# FPGA_IO.net
KiCad netlist of a schematic drawn in Altium Designer
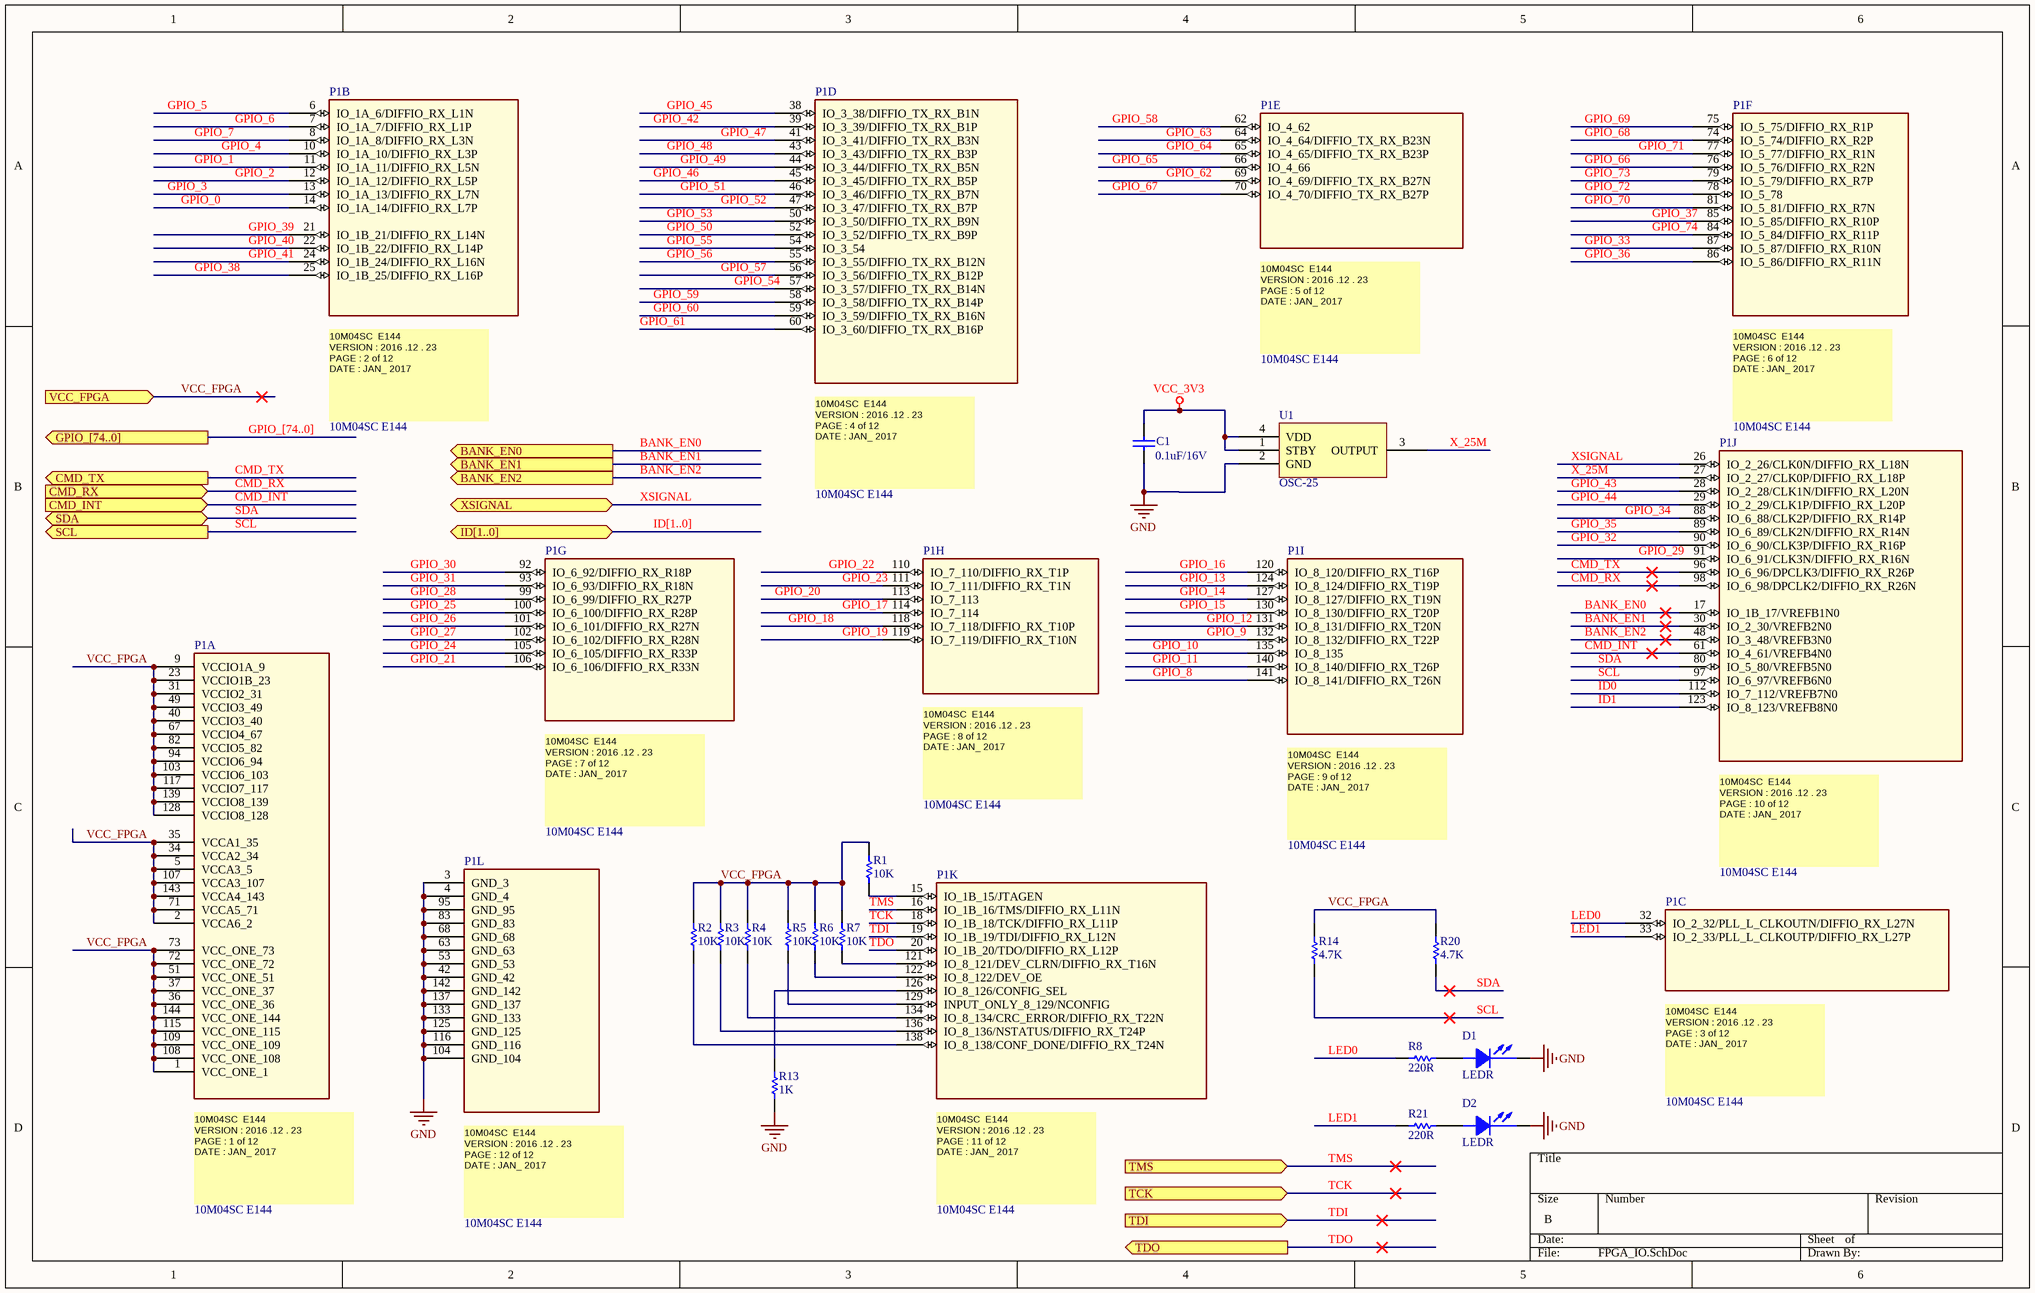
[diagram p0: FPGA_IO.SchDoc]

(export (version "E")
  (design (tool "Eeschema 10.0.6"))
  (components
    (comp (ref "C1")
      (value "0.1uF/16V")
      (footprint "0603C")
      (description "Multilayer Ceramic Capacitors MLCC - SMD/SMT 0603 16VDC 0.1uF 10% X7R AEC-Q200")
      (fields (field (name "MFR") "Taiyo Yuden") (field (name "MFR PART NO") "EMK107B7104KAHT"))
      (libsource (lib "Miscellaneous Devices") (part "Cap"))
    )
    (comp (ref "D1")
      (value "LEDR")
      (footprint "LED_0603")
      (description "Standard LEDs - SMD Red 631nm 14mcd 5mA")
      (fields (field (name "MFR") "Lite-On") (field (name "MFR PART NO") "LTST-C193KRKT-5A"))
      (libsource (lib "de20") (part "LED"))
    )
    (comp (ref "D2")
      (value "LEDR")
      (footprint "LED_0603")
      (description "Standard LEDs - SMD Red 631nm 14mcd 5mA")
      (fields (field (name "MFR") "Lite-On") (field (name "MFR PART NO") "LTST-C193KRKT-5A"))
      (libsource (lib "de20") (part "LED"))
    )
    (comp (ref "P1")
      (value "10M04SC E144")
      (footprint "10M04SCE144C8G")
      (description "FPGA - Field Programmable Gate Array non-volatile FPGA, 101 I/O, 144EQFP")
      (fields (field (name "MFR") "Intel / Altera") (field (name "MFR PART NO") "10M04SCE144C8G"))
      (libsource (lib "10m04sc_Library") (part "10M04SC E144"))
    )
    (comp (ref "R1")
      (value "10K")
      (footprint "0603R")
      (description "Thick Film Resistors - SMD 0603 10Kohms 1% Anti-Sulfur AEC-Q200")
      (fields (field (name "MFR") "ROHM Semiconductor") (field (name "MFR PART NO") "SFR03EZPF1002"))
      (libsource (lib "Miscellaneous Devices") (part "Res1"))
    )
    (comp (ref "R2")
      (value "10K")
      (footprint "0603R")
      (description "Thick Film Resistors - SMD 0603 10Kohms 1% Anti-Sulfur AEC-Q200")
      (fields (field (name "MFR") "ROHM Semiconductor") (field (name "MFR PART NO") "SFR03EZPF1002"))
      (libsource (lib "Miscellaneous Devices") (part "Res1"))
    )
    (comp (ref "R3")
      (value "10K")
      (footprint "0603R")
      (description "Thick Film Resistors - SMD 0603 10Kohms 1% Anti-Sulfur AEC-Q200")
      (fields (field (name "MFR") "ROHM Semiconductor") (field (name "MFR PART NO") "SFR03EZPF1002"))
      (libsource (lib "Miscellaneous Devices") (part "Res1"))
    )
    (comp (ref "R4")
      (value "10K")
      (footprint "0603R")
      (description "Thick Film Resistors - SMD 0603 10Kohms 1% Anti-Sulfur AEC-Q200")
      (fields (field (name "MFR") "ROHM Semiconductor") (field (name "MFR PART NO") "SFR03EZPF1002"))
      (libsource (lib "Miscellaneous Devices") (part "Res1"))
    )
    (comp (ref "R5")
      (value "10K")
      (footprint "0603R")
      (description "Thick Film Resistors - SMD 0603 10Kohms 1% Anti-Sulfur AEC-Q200")
      (fields (field (name "MFR") "ROHM Semiconductor") (field (name "MFR PART NO") "SFR03EZPF1002"))
      (libsource (lib "Miscellaneous Devices") (part "Res1"))
    )
    (comp (ref "R6")
      (value "10K")
      (footprint "0603R")
      (description "Thick Film Resistors - SMD 0603 10Kohms 1% Anti-Sulfur AEC-Q200")
      (fields (field (name "MFR") "ROHM Semiconductor") (field (name "MFR PART NO") "SFR03EZPF1002"))
      (libsource (lib "Miscellaneous Devices") (part "Res1"))
    )
    (comp (ref "R7")
      (value "10K")
      (footprint "0603R")
      (description "Thick Film Resistors - SMD 0603 10Kohms 1% Anti-Sulfur AEC-Q200")
      (fields (field (name "MFR") "ROHM Semiconductor") (field (name "MFR PART NO") "SFR03EZPF1002"))
      (libsource (lib "Miscellaneous Devices") (part "Res1"))
    )
    (comp (ref "R8")
      (value "220R")
      (footprint "0603R")
      (description "Thick Film Resistors - SMD 1/10Watt 220ohms 5% Commercial Use")
      (fields (field (name "MFR") "Vishay / Dale") (field (name "MFR PART NO") "CRCW0603220RJNEAC"))
      (libsource (lib "Miscellaneous Devices") (part "Res1"))
    )
    (comp (ref "R13")
      (value "1K")
      (footprint "0603R")
      (description "Resistor")
      (fields (field (name "MFR") "Vishay / Dale") (field (name "MFR PART NO") "CRCW06031K00FKEAC"))
      (libsource (lib "Miscellaneous Devices") (part "Res1"))
    )
    (comp (ref "R14")
      (value "4.7K")
      (footprint "0603R")
      (description "Thick Film Resistors - SMD 1/10Watt 4.7Kohms 5% Commercial Use")
      (fields (field (name "MFR") "Vishay / Dale") (field (name "MFR PART NO") "CRCW06034K70JNEAC"))
      (libsource (lib "Miscellaneous Devices") (part "Res1"))
    )
    (comp (ref "R20")
      (value "4.7K")
      (footprint "0603R")
      (description "Thick Film Resistors - SMD 1/10Watt 4.7Kohms 5% Commercial Use")
      (fields (field (name "MFR") "Vishay / Dale") (field (name "MFR PART NO") "CRCW06034K70JNEAC"))
      (libsource (lib "Miscellaneous Devices") (part "Res1"))
    )
    (comp (ref "R21")
      (value "220R")
      (footprint "0603R")
      (description "Thick Film Resistors - SMD 1/10Watt 220ohms 5% Commercial Use")
      (fields (field (name "MFR") "Vishay / Dale") (field (name "MFR PART NO") "CRCW0603220RJNEAC"))
      (libsource (lib "Miscellaneous Devices") (part "Res1"))
    )
    (comp (ref "U1")
      (value "OSC-25")
      (footprint "ASE-25.000MHZ-LC-T")
      (description "Standard Clock Oscillators 25.0 MHZ 3.3V 50PPM SMD 32")
      (fields (field (name "MFR") "ABRACON") (field (name "MFR PART NO") "ASE-25.000MHZ-LC-T"))
      (libsource (lib "Schlib1") (part "CRYSTAL"))
    )
  )
  (nets
    (net (code "1") (name "/BANK_EN0") (class "Default")
      (node (ref "P1") (pin "17") (pinfunction "IO_1B_17/VREFB1N0_17") (pintype "bidirectional"))
    )
    (net (code "2") (name "/BANK_EN1") (class "Default")
      (node (ref "P1") (pin "30") (pinfunction "IO_2_30/VREFB2N0_30") (pintype "bidirectional"))
    )
    (net (code "3") (name "/BANK_EN2") (class "Default")
      (node (ref "P1") (pin "48") (pinfunction "IO_3_48/VREFB3N0_48") (pintype "bidirectional"))
    )
    (net (code "4") (name "/CMD_INT") (class "Default")
      (node (ref "P1") (pin "61") (pinfunction "IO_4_61/VREFB4N0_61") (pintype "bidirectional"))
    )
    (net (code "5") (name "/CMD_RX") (class "Default")
      (node (ref "P1") (pin "98") (pinfunction "IO_6_98/DPCLK2/DIFFIO_RX_R26N_98") (pintype "bidirectional"))
    )
    (net (code "6") (name "/CMD_TX") (class "Default")
      (node (ref "P1") (pin "96") (pinfunction "IO_6_96/DPCLK3/DIFFIO_RX_R26P_96") (pintype "bidirectional"))
    )
    (net (code "7") (name "/GPIO_0") (class "Default")
      (node (ref "P1") (pin "14") (pinfunction "IO_1A_14/DIFFIO_RX_L7P_14") (pintype "bidirectional"))
    )
    (net (code "8") (name "/GPIO_1") (class "Default")
      (node (ref "P1") (pin "11") (pinfunction "IO_1A_11/DIFFIO_RX_L5N_11") (pintype "bidirectional"))
    )
    (net (code "9") (name "/GPIO_2") (class "Default")
      (node (ref "P1") (pin "12") (pinfunction "IO_1A_12/DIFFIO_RX_L5P_12") (pintype "bidirectional"))
    )
    (net (code "10") (name "/GPIO_3") (class "Default")
      (node (ref "P1") (pin "13") (pinfunction "IO_1A_13/DIFFIO_RX_L7N_13") (pintype "bidirectional"))
    )
    (net (code "11") (name "/GPIO_4") (class "Default")
      (node (ref "P1") (pin "10") (pinfunction "IO_1A_10/DIFFIO_RX_L3P_10") (pintype "bidirectional"))
    )
    (net (code "12") (name "/GPIO_5") (class "Default")
      (node (ref "P1") (pin "6") (pinfunction "IO_1A_6/DIFFIO_RX_L1N_6") (pintype "bidirectional"))
    )
    (net (code "13") (name "/GPIO_6") (class "Default")
      (node (ref "P1") (pin "7") (pinfunction "IO_1A_7/DIFFIO_RX_L1P_7") (pintype "bidirectional"))
    )
    (net (code "14") (name "/GPIO_7") (class "Default")
      (node (ref "P1") (pin "8") (pinfunction "IO_1A_8/DIFFIO_RX_L3N_8") (pintype "bidirectional"))
    )
    (net (code "15") (name "/GPIO_8") (class "Default")
      (node (ref "P1") (pin "141") (pinfunction "IO_8_141/DIFFIO_RX_T26N_141") (pintype "bidirectional"))
    )
    (net (code "16") (name "/GPIO_9") (class "Default")
      (node (ref "P1") (pin "132") (pinfunction "IO_8_132/DIFFIO_RX_T22P_132") (pintype "bidirectional"))
    )
    (net (code "17") (name "/GPIO_10") (class "Default")
      (node (ref "P1") (pin "135") (pinfunction "IO_8_135_135") (pintype "bidirectional"))
    )
    (net (code "18") (name "/GPIO_11") (class "Default")
      (node (ref "P1") (pin "140") (pinfunction "IO_8_140/DIFFIO_RX_T26P_140") (pintype "bidirectional"))
    )
    (net (code "19") (name "/GPIO_12") (class "Default")
      (node (ref "P1") (pin "131") (pinfunction "IO_8_131/DIFFIO_RX_T20N_131") (pintype "bidirectional"))
    )
    (net (code "20") (name "/GPIO_13") (class "Default")
      (node (ref "P1") (pin "124") (pinfunction "IO_8_124/DIFFIO_RX_T19P_124") (pintype "bidirectional"))
    )
    (net (code "21") (name "/GPIO_14") (class "Default")
      (node (ref "P1") (pin "127") (pinfunction "IO_8_127/DIFFIO_RX_T19N_127") (pintype "bidirectional"))
    )
    (net (code "22") (name "/GPIO_15") (class "Default")
      (node (ref "P1") (pin "130") (pinfunction "IO_8_130/DIFFIO_RX_T20P_130") (pintype "bidirectional"))
    )
    (net (code "23") (name "/GPIO_16") (class "Default")
      (node (ref "P1") (pin "120") (pinfunction "IO_8_120/DIFFIO_RX_T16P_120") (pintype "bidirectional"))
    )
    (net (code "24") (name "/GPIO_17") (class "Default")
      (node (ref "P1") (pin "114") (pinfunction "IO_7_114_114") (pintype "bidirectional"))
    )
    (net (code "25") (name "/GPIO_18") (class "Default")
      (node (ref "P1") (pin "118") (pinfunction "IO_7_118/DIFFIO_RX_T10P_118") (pintype "bidirectional"))
    )
    (net (code "26") (name "/GPIO_19") (class "Default")
      (node (ref "P1") (pin "119") (pinfunction "IO_7_119/DIFFIO_RX_T10N_119") (pintype "bidirectional"))
    )
    (net (code "27") (name "/GPIO_20") (class "Default")
      (node (ref "P1") (pin "113") (pinfunction "IO_7_113_113") (pintype "bidirectional"))
    )
    (net (code "28") (name "/GPIO_21") (class "Default")
      (node (ref "P1") (pin "106") (pinfunction "IO_6_106/DIFFIO_RX_R33N_106") (pintype "bidirectional"))
    )
    (net (code "29") (name "/GPIO_22") (class "Default")
      (node (ref "P1") (pin "110") (pinfunction "IO_7_110/DIFFIO_RX_T1P_110") (pintype "bidirectional"))
    )
    (net (code "30") (name "/GPIO_23") (class "Default")
      (node (ref "P1") (pin "111") (pinfunction "IO_7_111/DIFFIO_RX_T1N_111") (pintype "bidirectional"))
    )
    (net (code "31") (name "/GPIO_24") (class "Default")
      (node (ref "P1") (pin "105") (pinfunction "IO_6_105/DIFFIO_RX_R33P_105") (pintype "bidirectional"))
    )
    (net (code "32") (name "/GPIO_25") (class "Default")
      (node (ref "P1") (pin "100") (pinfunction "IO_6_100/DIFFIO_RX_R28P_100") (pintype "bidirectional"))
    )
    (net (code "33") (name "/GPIO_26") (class "Default")
      (node (ref "P1") (pin "101") (pinfunction "IO_6_101/DIFFIO_RX_R27N_101") (pintype "bidirectional"))
    )
    (net (code "34") (name "/GPIO_27") (class "Default")
      (node (ref "P1") (pin "102") (pinfunction "IO_6_102/DIFFIO_RX_R28N_102") (pintype "bidirectional"))
    )
    (net (code "35") (name "/GPIO_28") (class "Default")
      (node (ref "P1") (pin "99") (pinfunction "IO_6_99/DIFFIO_RX_R27P_99") (pintype "bidirectional"))
    )
    (net (code "36") (name "/GPIO_29") (class "Default")
      (node (ref "P1") (pin "91") (pinfunction "IO_6_91/CLK3N/DIFFIO_RX_R16N_91") (pintype "bidirectional"))
    )
    (net (code "37") (name "/GPIO_30") (class "Default")
      (node (ref "P1") (pin "92") (pinfunction "IO_6_92/DIFFIO_RX_R18P_92") (pintype "bidirectional"))
    )
    (net (code "38") (name "/GPIO_31") (class "Default")
      (node (ref "P1") (pin "93") (pinfunction "IO_6_93/DIFFIO_RX_R18N_93") (pintype "bidirectional"))
    )
    (net (code "39") (name "/GPIO_32") (class "Default")
      (node (ref "P1") (pin "90") (pinfunction "IO_6_90/CLK3P/DIFFIO_RX_R16P_90") (pintype "bidirectional"))
    )
    (net (code "40") (name "/GPIO_33") (class "Default")
      (node (ref "P1") (pin "87") (pinfunction "IO_5_87/DIFFIO_RX_R10N_87") (pintype "bidirectional"))
    )
    (net (code "41") (name "/GPIO_34") (class "Default")
      (node (ref "P1") (pin "88") (pinfunction "IO_6_88/CLK2P/DIFFIO_RX_R14P_88") (pintype "bidirectional"))
    )
    (net (code "42") (name "/GPIO_35") (class "Default")
      (node (ref "P1") (pin "89") (pinfunction "IO_6_89/CLK2N/DIFFIO_RX_R14N_89") (pintype "bidirectional"))
    )
    (net (code "43") (name "/GPIO_36") (class "Default")
      (node (ref "P1") (pin "86") (pinfunction "IO_5_86/DIFFIO_RX_R11N_86") (pintype "bidirectional"))
    )
    (net (code "44") (name "/GPIO_37") (class "Default")
      (node (ref "P1") (pin "85") (pinfunction "IO_5_85/DIFFIO_RX_R10P_85") (pintype "bidirectional"))
    )
    (net (code "45") (name "/GPIO_38") (class "Default")
      (node (ref "P1") (pin "25") (pinfunction "IO_1B_25/DIFFIO_RX_L16P_25") (pintype "bidirectional"))
    )
    (net (code "46") (name "/GPIO_39") (class "Default")
      (node (ref "P1") (pin "21") (pinfunction "IO_1B_21/DIFFIO_RX_L14N_21") (pintype "bidirectional"))
    )
    (net (code "47") (name "/GPIO_40") (class "Default")
      (node (ref "P1") (pin "22") (pinfunction "IO_1B_22/DIFFIO_RX_L14P_22") (pintype "bidirectional"))
    )
    (net (code "48") (name "/GPIO_41") (class "Default")
      (node (ref "P1") (pin "24") (pinfunction "IO_1B_24/DIFFIO_RX_L16N_24") (pintype "bidirectional"))
    )
    (net (code "49") (name "/GPIO_42") (class "Default")
      (node (ref "P1") (pin "39") (pinfunction "IO_3_39/DIFFIO_TX_RX_B1P_39") (pintype "bidirectional"))
    )
    (net (code "50") (name "/GPIO_43") (class "Default")
      (node (ref "P1") (pin "28") (pinfunction "IO_2_28/CLK1N/DIFFIO_RX_L20N_28") (pintype "bidirectional"))
    )
    (net (code "51") (name "/GPIO_44") (class "Default")
      (node (ref "P1") (pin "29") (pinfunction "IO_2_29/CLK1P/DIFFIO_RX_L20P_29") (pintype "bidirectional"))
    )
    (net (code "52") (name "/GPIO_45") (class "Default")
      (node (ref "P1") (pin "38") (pinfunction "IO_3_38/DIFFIO_TX_RX_B1N_38") (pintype "bidirectional"))
    )
    (net (code "53") (name "/GPIO_46") (class "Default")
      (node (ref "P1") (pin "45") (pinfunction "IO_3_45/DIFFIO_TX_RX_B5P_45") (pintype "bidirectional"))
    )
    (net (code "54") (name "/GPIO_47") (class "Default")
      (node (ref "P1") (pin "41") (pinfunction "IO_3_41/DIFFIO_TX_RX_B3N_41") (pintype "bidirectional"))
    )
    (net (code "55") (name "/GPIO_48") (class "Default")
      (node (ref "P1") (pin "43") (pinfunction "IO_3_43/DIFFIO_TX_RX_B3P_43") (pintype "bidirectional"))
    )
    (net (code "56") (name "/GPIO_49") (class "Default")
      (node (ref "P1") (pin "44") (pinfunction "IO_3_44/DIFFIO_TX_RX_B5N_44") (pintype "bidirectional"))
    )
    (net (code "57") (name "/GPIO_50") (class "Default")
      (node (ref "P1") (pin "52") (pinfunction "IO_3_52/DIFFIO_TX_RX_B9P_52") (pintype "bidirectional"))
    )
    (net (code "58") (name "/GPIO_51") (class "Default")
      (node (ref "P1") (pin "46") (pinfunction "IO_3_46/DIFFIO_TX_RX_B7N_46") (pintype "bidirectional"))
    )
    (net (code "59") (name "/GPIO_52") (class "Default")
      (node (ref "P1") (pin "47") (pinfunction "IO_3_47/DIFFIO_TX_RX_B7P_47") (pintype "bidirectional"))
    )
    (net (code "60") (name "/GPIO_53") (class "Default")
      (node (ref "P1") (pin "50") (pinfunction "IO_3_50/DIFFIO_TX_RX_B9N_50") (pintype "bidirectional"))
    )
    (net (code "61") (name "/GPIO_54") (class "Default")
      (node (ref "P1") (pin "57") (pinfunction "IO_3_57/DIFFIO_TX_RX_B14N_57") (pintype "bidirectional"))
    )
    (net (code "62") (name "/GPIO_55") (class "Default")
      (node (ref "P1") (pin "54") (pinfunction "IO_3_54_54") (pintype "bidirectional"))
    )
    (net (code "63") (name "/GPIO_56") (class "Default")
      (node (ref "P1") (pin "55") (pinfunction "IO_3_55/DIFFIO_TX_RX_B12N_55") (pintype "bidirectional"))
    )
    (net (code "64") (name "/GPIO_57") (class "Default")
      (node (ref "P1") (pin "56") (pinfunction "IO_3_56/DIFFIO_TX_RX_B12P_56") (pintype "bidirectional"))
    )
    (net (code "65") (name "/GPIO_58") (class "Default")
      (node (ref "P1") (pin "62") (pinfunction "IO_4_62_62") (pintype "bidirectional"))
    )
    (net (code "66") (name "/GPIO_59") (class "Default")
      (node (ref "P1") (pin "58") (pinfunction "IO_3_58/DIFFIO_TX_RX_B14P_58") (pintype "bidirectional"))
    )
    (net (code "67") (name "/GPIO_60") (class "Default")
      (node (ref "P1") (pin "59") (pinfunction "IO_3_59/DIFFIO_TX_RX_B16N_59") (pintype "bidirectional"))
    )
    (net (code "68") (name "/GPIO_61") (class "Default")
      (node (ref "P1") (pin "60") (pinfunction "IO_3_60/DIFFIO_TX_RX_B16P_60") (pintype "bidirectional"))
    )
    (net (code "69") (name "/GPIO_62") (class "Default")
      (node (ref "P1") (pin "69") (pinfunction "IO_4_69/DIFFIO_TX_RX_B27N_69") (pintype "bidirectional"))
    )
    (net (code "70") (name "/GPIO_63") (class "Default")
      (node (ref "P1") (pin "64") (pinfunction "IO_4_64/DIFFIO_TX_RX_B23N_64") (pintype "bidirectional"))
    )
    (net (code "71") (name "/GPIO_64") (class "Default")
      (node (ref "P1") (pin "65") (pinfunction "IO_4_65/DIFFIO_TX_RX_B23P_65") (pintype "bidirectional"))
    )
    (net (code "72") (name "/GPIO_65") (class "Default")
      (node (ref "P1") (pin "66") (pinfunction "IO_4_66_66") (pintype "bidirectional"))
    )
    (net (code "73") (name "/GPIO_66") (class "Default")
      (node (ref "P1") (pin "76") (pinfunction "IO_5_76/DIFFIO_RX_R2N_76") (pintype "bidirectional"))
    )
    (net (code "74") (name "/GPIO_67") (class "Default")
      (node (ref "P1") (pin "70") (pinfunction "IO_4_70/DIFFIO_TX_RX_B27P_70") (pintype "bidirectional"))
    )
    (net (code "75") (name "/GPIO_68") (class "Default")
      (node (ref "P1") (pin "74") (pinfunction "IO_5_74/DIFFIO_RX_R2P_74") (pintype "bidirectional"))
    )
    (net (code "76") (name "/GPIO_69") (class "Default")
      (node (ref "P1") (pin "75") (pinfunction "IO_5_75/DIFFIO_RX_R1P_75") (pintype "bidirectional"))
    )
    (net (code "77") (name "/GPIO_70") (class "Default")
      (node (ref "P1") (pin "81") (pinfunction "IO_5_81/DIFFIO_RX_R7N_81") (pintype "bidirectional"))
    )
    (net (code "78") (name "/GPIO_71") (class "Default")
      (node (ref "P1") (pin "77") (pinfunction "IO_5_77/DIFFIO_RX_R1N_77") (pintype "bidirectional"))
    )
    (net (code "79") (name "/GPIO_72") (class "Default")
      (node (ref "P1") (pin "78") (pinfunction "IO_5_78_78") (pintype "bidirectional"))
    )
    (net (code "80") (name "/GPIO_73") (class "Default")
      (node (ref "P1") (pin "79") (pinfunction "IO_5_79/DIFFIO_RX_R7P_79") (pintype "bidirectional"))
    )
    (net (code "81") (name "/GPIO_74") (class "Default")
      (node (ref "P1") (pin "84") (pinfunction "IO_5_84/DIFFIO_RX_R11P_84") (pintype "bidirectional"))
    )
    (net (code "83") (name "/ID0") (class "Default")
      (node (ref "P1") (pin "112") (pinfunction "IO_7_112/VREFB7N0_112") (pintype "bidirectional"))
    )
    (net (code "84") (name "/ID1") (class "Default")
      (node (ref "P1") (pin "123") (pinfunction "IO_8_123/VREFB8N0_123") (pintype "bidirectional"))
    )
    (net (code "86") (name "/LED0") (class "Default")
      (node (ref "P1") (pin "32") (pinfunction "IO_2_32/PLL_L_CLKOUTN/DIFFIO_RX_L27N_32") (pintype "bidirectional"))
      (node (ref "R8") (pin "2") (pinfunction "2_2") (pintype "passive"))
    )
    (net (code "87") (name "/LED1") (class "Default")
      (node (ref "P1") (pin "33") (pinfunction "IO_2_33/PLL_L_CLKOUTP/DIFFIO_RX_L27P_33") (pintype "bidirectional"))
      (node (ref "R21") (pin "2") (pinfunction "2_2") (pintype "passive"))
    )
    (net (code "88") (name "/SCL") (class "Default")
      (node (ref "P1") (pin "97") (pinfunction "IO_6_97/VREFB6N0_97") (pintype "bidirectional"))
      (node (ref "R14") (pin "1") (pinfunction "1_1") (pintype "passive"))
    )
    (net (code "89") (name "/SDA") (class "Default")
      (node (ref "P1") (pin "80") (pinfunction "IO_5_80/VREFB5N0_80") (pintype "bidirectional"))
      (node (ref "R20") (pin "1") (pinfunction "1_1") (pintype "passive"))
    )
    (net (code "90") (name "/TCK") (class "Default")
      (node (ref "P1") (pin "18") (pinfunction "IO_1B_18/TCK/DIFFIO_RX_L11P_18") (pintype "bidirectional"))
    )
    (net (code "91") (name "/TDI") (class "Default")
      (node (ref "P1") (pin "19") (pinfunction "IO_1B_19/TDI/DIFFIO_RX_L12N_19") (pintype "bidirectional"))
    )
    (net (code "92") (name "/TDO") (class "Default")
      (node (ref "P1") (pin "20") (pinfunction "IO_1B_20/TDO/DIFFIO_RX_L12P_20") (pintype "bidirectional"))
    )
    (net (code "93") (name "/TMS") (class "Default")
      (node (ref "P1") (pin "16") (pinfunction "IO_1B_16/TMS/DIFFIO_RX_L11N_16") (pintype "bidirectional"))
    )
    (net (code "94") (name "/VCC_FPGA") (class "Default")
      (node (ref "P1") (pin "1") (pinfunction "VCC_ONE_1_1") (pintype "power_in"))
      (node (ref "P1") (pin "103") (pinfunction "VCCIO6_103_103") (pintype "power_in"))
      (node (ref "P1") (pin "107") (pinfunction "VCCA3_107_107") (pintype "power_in"))
      (node (ref "P1") (pin "108") (pinfunction "VCC_ONE_108_108") (pintype "power_in"))
      (node (ref "P1") (pin "109") (pinfunction "VCC_ONE_109_109") (pintype "power_in"))
      (node (ref "P1") (pin "115") (pinfunction "VCC_ONE_115_115") (pintype "power_in"))
      (node (ref "P1") (pin "117") (pinfunction "VCCIO7_117_117") (pintype "power_in"))
      (node (ref "P1") (pin "128") (pinfunction "VCCIO8_128_128") (pintype "power_in"))
      (node (ref "P1") (pin "139") (pinfunction "VCCIO8_139_139") (pintype "power_in"))
      (node (ref "P1") (pin "143") (pinfunction "VCCA4_143_143") (pintype "power_in"))
      (node (ref "P1") (pin "144") (pinfunction "VCC_ONE_144_144") (pintype "power_in"))
      (node (ref "P1") (pin "2") (pinfunction "VCCA6_2_2") (pintype "power_in"))
      (node (ref "P1") (pin "23") (pinfunction "VCCIO1B_23_23") (pintype "power_in"))
      (node (ref "P1") (pin "31") (pinfunction "VCCIO2_31_31") (pintype "power_in"))
      (node (ref "P1") (pin "34") (pinfunction "VCCA2_34_34") (pintype "power_in"))
      (node (ref "P1") (pin "35") (pinfunction "VCCA1_35_35") (pintype "power_in"))
      (node (ref "P1") (pin "36") (pinfunction "VCC_ONE_36_36") (pintype "power_in"))
      (node (ref "P1") (pin "37") (pinfunction "VCC_ONE_37_37") (pintype "power_in"))
      (node (ref "P1") (pin "40") (pinfunction "VCCIO3_40_40") (pintype "power_in"))
      (node (ref "P1") (pin "49") (pinfunction "VCCIO3_49_49") (pintype "power_in"))
      (node (ref "P1") (pin "5") (pinfunction "VCCA3_5_5") (pintype "power_in"))
      (node (ref "P1") (pin "51") (pinfunction "VCC_ONE_51_51") (pintype "power_in"))
      (node (ref "P1") (pin "67") (pinfunction "VCCIO4_67_67") (pintype "power_in"))
      (node (ref "P1") (pin "71") (pinfunction "VCCA5_71_71") (pintype "power_in"))
      (node (ref "P1") (pin "72") (pinfunction "VCC_ONE_72_72") (pintype "power_in"))
      (node (ref "P1") (pin "73") (pinfunction "VCC_ONE_73_73") (pintype "power_in"))
      (node (ref "P1") (pin "82") (pinfunction "VCCIO5_82_82") (pintype "power_in"))
      (node (ref "P1") (pin "9") (pinfunction "VCCIO1A_9_9") (pintype "power_in"))
      (node (ref "P1") (pin "94") (pinfunction "VCCIO6_94_94") (pintype "power_in"))
      (node (ref "R1") (pin "1") (pinfunction "1_1") (pintype "passive"))
      (node (ref "R14") (pin "2") (pinfunction "2_2") (pintype "passive"))
      (node (ref "R2") (pin "1") (pinfunction "1_1") (pintype "passive"))
      (node (ref "R20") (pin "2") (pinfunction "2_2") (pintype "passive"))
      (node (ref "R3") (pin "1") (pinfunction "1_1") (pintype "passive"))
      (node (ref "R4") (pin "1") (pinfunction "1_1") (pintype "passive"))
      (node (ref "R5") (pin "1") (pinfunction "1_1") (pintype "passive"))
      (node (ref "R6") (pin "1") (pinfunction "1_1") (pintype "passive"))
      (node (ref "R7") (pin "1") (pinfunction "1_1") (pintype "passive"))
    )
    (net (code "95") (name "/XSIGNAL") (class "Default")
      (node (ref "P1") (pin "26") (pinfunction "IO_2_26/CLK0N/DIFFIO_RX_L18N_26") (pintype "bidirectional"))
    )
    (net (code "96") (name "/X_25M") (class "Default")
      (node (ref "P1") (pin "27") (pinfunction "IO_2_27/CLK0P/DIFFIO_RX_L18P_27") (pintype "bidirectional"))
      (node (ref "U1") (pin "3") (pinfunction "OUTPUT_3") (pintype "passive"))
    )
    (net (code "97") (name "GND") (class "Default")
      (node (ref "C1") (pin "1") (pinfunction "1_1") (pintype "passive"))
      (node (ref "D1") (pin "2") (pinfunction "CATHODE_2") (pintype "passive"))
      (node (ref "D2") (pin "2") (pinfunction "CATHODE_2") (pintype "passive"))
      (node (ref "P1") (pin "104") (pinfunction "GND_104_104") (pintype "power_in"))
      (node (ref "P1") (pin "116") (pinfunction "GND_116_116") (pintype "power_in"))
      (node (ref "P1") (pin "125") (pinfunction "GND_125_125") (pintype "power_in"))
      (node (ref "P1") (pin "133") (pinfunction "GND_133_133") (pintype "power_in"))
      (node (ref "P1") (pin "137") (pinfunction "GND_137_137") (pintype "power_in"))
      (node (ref "P1") (pin "142") (pinfunction "GND_142_142") (pintype "power_in"))
      (node (ref "P1") (pin "3") (pinfunction "GND_3_3") (pintype "power_in"))
      (node (ref "P1") (pin "4") (pinfunction "GND_4_4") (pintype "power_in"))
      (node (ref "P1") (pin "42") (pinfunction "GND_42_42") (pintype "power_in"))
      (node (ref "P1") (pin "53") (pinfunction "GND_53_53") (pintype "power_in"))
      (node (ref "P1") (pin "63") (pinfunction "GND_63_63") (pintype "power_in"))
      (node (ref "P1") (pin "68") (pinfunction "GND_68_68") (pintype "power_in"))
      (node (ref "P1") (pin "83") (pinfunction "GND_83_83") (pintype "power_in"))
      (node (ref "P1") (pin "95") (pinfunction "GND_95_95") (pintype "power_in"))
      (node (ref "R13") (pin "1") (pinfunction "1_1") (pintype "passive"))
      (node (ref "U1") (pin "2") (pinfunction "GND_2") (pintype "passive"))
    )
    (net (code "98") (name "Net-(D1-ANODE)") (class "Default")
      (node (ref "D1") (pin "1") (pinfunction "ANODE_1") (pintype "passive"))
      (node (ref "R8") (pin "1") (pinfunction "1_1") (pintype "passive"))
    )
    (net (code "99") (name "Net-(D2-ANODE)") (class "Default")
      (node (ref "D2") (pin "1") (pinfunction "ANODE_1") (pintype "passive"))
      (node (ref "R21") (pin "1") (pinfunction "1_1") (pintype "passive"))
    )
    (net (code "100") (name "Net-(P1K-INPUT_ONLY_8_129{slash}NCONFIG)") (class "Default")
      (node (ref "P1") (pin "129") (pinfunction "INPUT_ONLY_8_129/NCONFIG_129") (pintype "bidirectional"))
      (node (ref "R5") (pin "2") (pinfunction "2_2") (pintype "passive"))
    )
    (net (code "101") (name "Net-(P1K-IO_1B_15{slash}JTAGEN)") (class "Default")
      (node (ref "P1") (pin "15") (pinfunction "IO_1B_15/JTAGEN_15") (pintype "bidirectional"))
      (node (ref "R1") (pin "2") (pinfunction "2_2") (pintype "passive"))
    )
    (net (code "102") (name "Net-(P1K-IO_8_121{slash}DEV_CLRN{slash}DIFFIO_RX_T16N)") (class "Default")
      (node (ref "P1") (pin "121") (pinfunction "IO_8_121/DEV_CLRN/DIFFIO_RX_T16N_121") (pintype "bidirectional"))
      (node (ref "R7") (pin "2") (pinfunction "2_2") (pintype "passive"))
    )
    (net (code "103") (name "Net-(P1K-IO_8_122{slash}DEV_OE)") (class "Default")
      (node (ref "P1") (pin "122") (pinfunction "IO_8_122/DEV_OE_122") (pintype "bidirectional"))
      (node (ref "R6") (pin "2") (pinfunction "2_2") (pintype "passive"))
    )
    (net (code "104") (name "Net-(P1K-IO_8_126{slash}CONFIG_SEL)") (class "Default")
      (node (ref "P1") (pin "126") (pinfunction "IO_8_126/CONFIG_SEL_126") (pintype "bidirectional"))
      (node (ref "R13") (pin "2") (pinfunction "2_2") (pintype "passive"))
    )
    (net (code "105") (name "Net-(P1K-IO_8_134{slash}CRC_ERROR{slash}DIFFIO_RX_T22N)") (class "Default")
      (node (ref "P1") (pin "134") (pinfunction "IO_8_134/CRC_ERROR/DIFFIO_RX_T22N_134") (pintype "bidirectional"))
      (node (ref "R4") (pin "2") (pinfunction "2_2") (pintype "passive"))
    )
    (net (code "106") (name "Net-(P1K-IO_8_136{slash}NSTATUS{slash}DIFFIO_RX_T24P)") (class "Default")
      (node (ref "P1") (pin "136") (pinfunction "IO_8_136/NSTATUS/DIFFIO_RX_T24P_136") (pintype "bidirectional"))
      (node (ref "R3") (pin "2") (pinfunction "2_2") (pintype "passive"))
    )
    (net (code "107") (name "Net-(P1K-IO_8_138{slash}CONF_DONE{slash}DIFFIO_RX_T24N)") (class "Default")
      (node (ref "P1") (pin "138") (pinfunction "IO_8_138/CONF_DONE/DIFFIO_RX_T24N_138") (pintype "bidirectional"))
      (node (ref "R2") (pin "2") (pinfunction "2_2") (pintype "passive"))
    )
    (net (code "108") (name "VCC_3V3") (class "Default")
      (node (ref "C1") (pin "2") (pinfunction "2_2") (pintype "passive"))
      (node (ref "U1") (pin "1") (pinfunction "STBY_1") (pintype "passive"))
      (node (ref "U1") (pin "4") (pinfunction "VDD_4") (pintype "passive"))
    )
  )
)
